# calculator.net
KiCad netlist of a schematic drawn in EAGLE
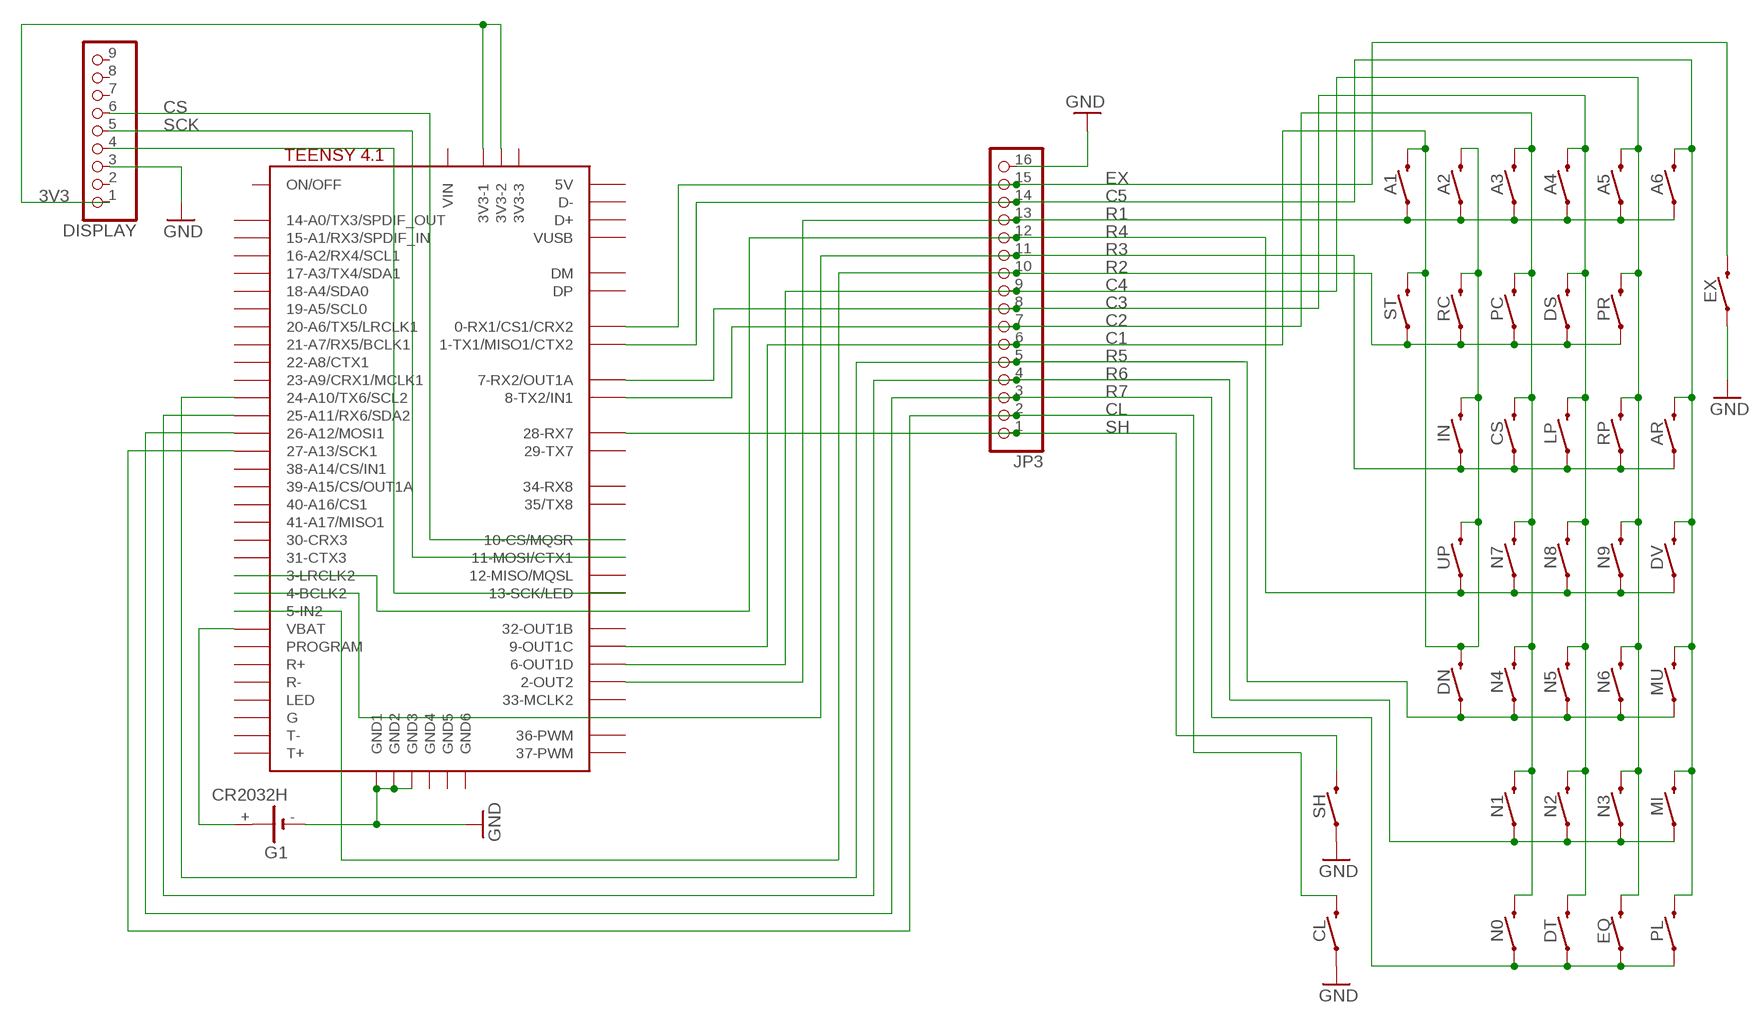
[diagram p0: schematic, sheet 1]

(export (version "E")
  (design (tool "Eeschema 10.0.6"))
  (components
    (comp (ref "A1")
      (value "MOMENTARY-SWITCH-SPST-PTH-6.0MM")
      (footprint "eagle-import:TACTILE_SWITCH_PTH_6.0MM")
      (libsource (lib "eagle-import") (part "MOMENTARY-SWITCH-SPST-PTH-6.0MM"))
    )
    (comp (ref "A2")
      (value "MOMENTARY-SWITCH-SPST-PTH-6.0MM")
      (footprint "eagle-import:TACTILE_SWITCH_PTH_6.0MM")
      (libsource (lib "eagle-import") (part "MOMENTARY-SWITCH-SPST-PTH-6.0MM"))
    )
    (comp (ref "A3")
      (value "MOMENTARY-SWITCH-SPST-PTH-6.0MM")
      (footprint "eagle-import:TACTILE_SWITCH_PTH_6.0MM")
      (libsource (lib "eagle-import") (part "MOMENTARY-SWITCH-SPST-PTH-6.0MM"))
    )
    (comp (ref "A4")
      (value "MOMENTARY-SWITCH-SPST-PTH-6.0MM")
      (footprint "eagle-import:TACTILE_SWITCH_PTH_6.0MM")
      (libsource (lib "eagle-import") (part "MOMENTARY-SWITCH-SPST-PTH-6.0MM"))
    )
    (comp (ref "A5")
      (value "MOMENTARY-SWITCH-SPST-PTH-6.0MM")
      (footprint "eagle-import:TACTILE_SWITCH_PTH_6.0MM")
      (libsource (lib "eagle-import") (part "MOMENTARY-SWITCH-SPST-PTH-6.0MM"))
    )
    (comp (ref "A6")
      (value "MOMENTARY-SWITCH-SPST-PTH-6.0MM")
      (footprint "eagle-import:TACTILE_SWITCH_PTH_6.0MM")
      (libsource (lib "eagle-import") (part "MOMENTARY-SWITCH-SPST-PTH-6.0MM"))
    )
    (comp (ref "AR")
      (value "MOMENTARY-SWITCH-SPST-PTH-6.0MM")
      (footprint "eagle-import:TACTILE_SWITCH_PTH_6.0MM")
      (libsource (lib "eagle-import") (part "MOMENTARY-SWITCH-SPST-PTH-6.0MM"))
    )
    (comp (ref "CL")
      (value "MOMENTARY-SWITCH-SPST-PTH-6.0MM")
      (footprint "eagle-import:TACTILE_SWITCH_PTH_6.0MM")
      (libsource (lib "eagle-import") (part "MOMENTARY-SWITCH-SPST-PTH-6.0MM"))
    )
    (comp (ref "CS")
      (value "MOMENTARY-SWITCH-SPST-PTH-6.0MM")
      (footprint "eagle-import:TACTILE_SWITCH_PTH_6.0MM")
      (libsource (lib "eagle-import") (part "MOMENTARY-SWITCH-SPST-PTH-6.0MM"))
    )
    (comp (ref "DISPLAY")
      (value "PINHD-1X9")
      (footprint "eagle-import:1X09-BIG")
      (libsource (lib "eagle-import") (part "PINHD-1X9"))
    )
    (comp (ref "DN")
      (value "MOMENTARY-SWITCH-SPST-PTH-6.0MM")
      (footprint "eagle-import:TACTILE_SWITCH_PTH_6.0MM")
      (libsource (lib "eagle-import") (part "MOMENTARY-SWITCH-SPST-PTH-6.0MM"))
    )
    (comp (ref "DS")
      (value "MOMENTARY-SWITCH-SPST-PTH-6.0MM")
      (footprint "eagle-import:TACTILE_SWITCH_PTH_6.0MM")
      (libsource (lib "eagle-import") (part "MOMENTARY-SWITCH-SPST-PTH-6.0MM"))
    )
    (comp (ref "DT")
      (value "MOMENTARY-SWITCH-SPST-PTH-6.0MM")
      (footprint "eagle-import:TACTILE_SWITCH_PTH_6.0MM")
      (libsource (lib "eagle-import") (part "MOMENTARY-SWITCH-SPST-PTH-6.0MM"))
    )
    (comp (ref "DV")
      (value "MOMENTARY-SWITCH-SPST-PTH-6.0MM")
      (footprint "eagle-import:TACTILE_SWITCH_PTH_6.0MM")
      (libsource (lib "eagle-import") (part "MOMENTARY-SWITCH-SPST-PTH-6.0MM"))
    )
    (comp (ref "EQ")
      (value "MOMENTARY-SWITCH-SPST-PTH-6.0MM")
      (footprint "eagle-import:TACTILE_SWITCH_PTH_6.0MM")
      (libsource (lib "eagle-import") (part "MOMENTARY-SWITCH-SPST-PTH-6.0MM"))
    )
    (comp (ref "EX")
      (value "MOMENTARY-SWITCH-SPST-PTH-6.0MM")
      (footprint "eagle-import:TACTILE_SWITCH_PTH_6.0MM")
      (libsource (lib "eagle-import") (part "MOMENTARY-SWITCH-SPST-PTH-6.0MM"))
    )
    (comp (ref "G1")
      (value "CR2032H")
      (footprint "eagle-import:CR2032H")
      (libsource (lib "eagle-import") (part "CR2032H"))
    )
    (comp (ref "IN")
      (value "MOMENTARY-SWITCH-SPST-PTH-6.0MM")
      (footprint "eagle-import:TACTILE_SWITCH_PTH_6.0MM")
      (libsource (lib "eagle-import") (part "MOMENTARY-SWITCH-SPST-PTH-6.0MM"))
    )
    (comp (ref "JP3")
      (value "PINHD-1X16")
      (footprint "eagle-import:1X16")
      (libsource (lib "eagle-import") (part "PINHD-1X16"))
    )
    (comp (ref "LP")
      (value "MOMENTARY-SWITCH-SPST-PTH-6.0MM")
      (footprint "eagle-import:TACTILE_SWITCH_PTH_6.0MM")
      (libsource (lib "eagle-import") (part "MOMENTARY-SWITCH-SPST-PTH-6.0MM"))
    )
    (comp (ref "MI")
      (value "MOMENTARY-SWITCH-SPST-PTH-6.0MM")
      (footprint "eagle-import:TACTILE_SWITCH_PTH_6.0MM")
      (libsource (lib "eagle-import") (part "MOMENTARY-SWITCH-SPST-PTH-6.0MM"))
    )
    (comp (ref "MU")
      (value "MOMENTARY-SWITCH-SPST-PTH-6.0MM")
      (footprint "eagle-import:TACTILE_SWITCH_PTH_6.0MM")
      (libsource (lib "eagle-import") (part "MOMENTARY-SWITCH-SPST-PTH-6.0MM"))
    )
    (comp (ref "N0")
      (value "MOMENTARY-SWITCH-SPST-PTH-6.0MM")
      (footprint "eagle-import:TACTILE_SWITCH_PTH_6.0MM")
      (libsource (lib "eagle-import") (part "MOMENTARY-SWITCH-SPST-PTH-6.0MM"))
    )
    (comp (ref "N1")
      (value "MOMENTARY-SWITCH-SPST-PTH-6.0MM")
      (footprint "eagle-import:TACTILE_SWITCH_PTH_6.0MM")
      (libsource (lib "eagle-import") (part "MOMENTARY-SWITCH-SPST-PTH-6.0MM"))
    )
    (comp (ref "N2")
      (value "MOMENTARY-SWITCH-SPST-PTH-6.0MM")
      (footprint "eagle-import:TACTILE_SWITCH_PTH_6.0MM")
      (libsource (lib "eagle-import") (part "MOMENTARY-SWITCH-SPST-PTH-6.0MM"))
    )
    (comp (ref "N3")
      (value "MOMENTARY-SWITCH-SPST-PTH-6.0MM")
      (footprint "eagle-import:TACTILE_SWITCH_PTH_6.0MM")
      (libsource (lib "eagle-import") (part "MOMENTARY-SWITCH-SPST-PTH-6.0MM"))
    )
    (comp (ref "N4")
      (value "MOMENTARY-SWITCH-SPST-PTH-6.0MM")
      (footprint "eagle-import:TACTILE_SWITCH_PTH_6.0MM")
      (libsource (lib "eagle-import") (part "MOMENTARY-SWITCH-SPST-PTH-6.0MM"))
    )
    (comp (ref "N5")
      (value "MOMENTARY-SWITCH-SPST-PTH-6.0MM")
      (footprint "eagle-import:TACTILE_SWITCH_PTH_6.0MM")
      (libsource (lib "eagle-import") (part "MOMENTARY-SWITCH-SPST-PTH-6.0MM"))
    )
    (comp (ref "N6")
      (value "MOMENTARY-SWITCH-SPST-PTH-6.0MM")
      (footprint "eagle-import:TACTILE_SWITCH_PTH_6.0MM")
      (libsource (lib "eagle-import") (part "MOMENTARY-SWITCH-SPST-PTH-6.0MM"))
    )
    (comp (ref "N7")
      (value "MOMENTARY-SWITCH-SPST-PTH-6.0MM")
      (footprint "eagle-import:TACTILE_SWITCH_PTH_6.0MM")
      (libsource (lib "eagle-import") (part "MOMENTARY-SWITCH-SPST-PTH-6.0MM"))
    )
    (comp (ref "N8")
      (value "MOMENTARY-SWITCH-SPST-PTH-6.0MM")
      (footprint "eagle-import:TACTILE_SWITCH_PTH_6.0MM")
      (libsource (lib "eagle-import") (part "MOMENTARY-SWITCH-SPST-PTH-6.0MM"))
    )
    (comp (ref "N9")
      (value "MOMENTARY-SWITCH-SPST-PTH-6.0MM")
      (footprint "eagle-import:TACTILE_SWITCH_PTH_6.0MM")
      (libsource (lib "eagle-import") (part "MOMENTARY-SWITCH-SPST-PTH-6.0MM"))
    )
    (comp (ref "PC")
      (value "MOMENTARY-SWITCH-SPST-PTH-6.0MM")
      (footprint "eagle-import:TACTILE_SWITCH_PTH_6.0MM")
      (libsource (lib "eagle-import") (part "MOMENTARY-SWITCH-SPST-PTH-6.0MM"))
    )
    (comp (ref "PL")
      (value "MOMENTARY-SWITCH-SPST-PTH-6.0MM")
      (footprint "eagle-import:TACTILE_SWITCH_PTH_6.0MM")
      (libsource (lib "eagle-import") (part "MOMENTARY-SWITCH-SPST-PTH-6.0MM"))
    )
    (comp (ref "PR")
      (value "MOMENTARY-SWITCH-SPST-PTH-6.0MM")
      (footprint "eagle-import:TACTILE_SWITCH_PTH_6.0MM")
      (libsource (lib "eagle-import") (part "MOMENTARY-SWITCH-SPST-PTH-6.0MM"))
    )
    (comp (ref "RC")
      (value "MOMENTARY-SWITCH-SPST-PTH-6.0MM")
      (footprint "eagle-import:TACTILE_SWITCH_PTH_6.0MM")
      (libsource (lib "eagle-import") (part "MOMENTARY-SWITCH-SPST-PTH-6.0MM"))
    )
    (comp (ref "RP")
      (value "MOMENTARY-SWITCH-SPST-PTH-6.0MM")
      (footprint "eagle-import:TACTILE_SWITCH_PTH_6.0MM")
      (libsource (lib "eagle-import") (part "MOMENTARY-SWITCH-SPST-PTH-6.0MM"))
    )
    (comp (ref "SH")
      (value "MOMENTARY-SWITCH-SPST-PTH-6.0MM")
      (footprint "eagle-import:TACTILE_SWITCH_PTH_6.0MM")
      (libsource (lib "eagle-import") (part "MOMENTARY-SWITCH-SPST-PTH-6.0MM"))
    )
    (comp (ref "ST")
      (value "MOMENTARY-SWITCH-SPST-PTH-6.0MM")
      (footprint "eagle-import:TACTILE_SWITCH_PTH_6.0MM")
      (libsource (lib "eagle-import") (part "MOMENTARY-SWITCH-SPST-PTH-6.0MM"))
    )
    (comp (ref "U$1")
      (value "TEENSY41")
      (footprint "eagle-import:TEENSY41")
      (libsource (lib "eagle-import") (part "TEENSY41"))
    )
    (comp (ref "UP")
      (value "MOMENTARY-SWITCH-SPST-PTH-6.0MM")
      (footprint "eagle-import:TACTILE_SWITCH_PTH_6.0MM")
      (libsource (lib "eagle-import") (part "MOMENTARY-SWITCH-SPST-PTH-6.0MM"))
    )
  )
  (nets
    (net (code "1") (name "/3V3") (class "Default")
      (node (ref "DISPLAY") (pin "1") (pinfunction "1_1") (pintype "passive"))
      (node (ref "U$1") (pin "3V3-1") (pinfunction "3V3-1_3V3-1") (pintype "bidirectional"))
      (node (ref "U$1") (pin "3V3-2") (pinfunction "3V3-2_3V3-2") (pintype "bidirectional"))
    )
    (net (code "2") (name "/C1") (class "Default")
      (node (ref "A1") (pin "3") (pinfunction "2_3") (pintype "passive"))
      (node (ref "A2") (pin "3") (pinfunction "2_3") (pintype "passive"))
      (node (ref "DN") (pin "3") (pinfunction "2_3") (pintype "passive"))
      (node (ref "IN") (pin "3") (pinfunction "2_3") (pintype "passive"))
      (node (ref "JP3") (pin "6") (pinfunction "6_6") (pintype "passive"))
      (node (ref "RC") (pin "3") (pinfunction "2_3") (pintype "passive"))
      (node (ref "ST") (pin "3") (pinfunction "2_3") (pintype "passive"))
      (node (ref "U$1") (pin "9-OUT1C") (pinfunction "9-OUT1C_9-OUT1C") (pintype "bidirectional"))
      (node (ref "UP") (pin "3") (pinfunction "2_3") (pintype "passive"))
    )
    (net (code "3") (name "/C2") (class "Default")
      (node (ref "A3") (pin "3") (pinfunction "2_3") (pintype "passive"))
      (node (ref "CS") (pin "3") (pinfunction "2_3") (pintype "passive"))
      (node (ref "JP3") (pin "7") (pinfunction "7_7") (pintype "passive"))
      (node (ref "N0") (pin "3") (pinfunction "2_3") (pintype "passive"))
      (node (ref "N1") (pin "3") (pinfunction "2_3") (pintype "passive"))
      (node (ref "N4") (pin "3") (pinfunction "2_3") (pintype "passive"))
      (node (ref "N7") (pin "3") (pinfunction "2_3") (pintype "passive"))
      (node (ref "PC") (pin "3") (pinfunction "2_3") (pintype "passive"))
      (node (ref "U$1") (pin "8-TX2/IN2") (pinfunction "8-TX2/IN1_8-TX2/IN2") (pintype "bidirectional"))
    )
    (net (code "4") (name "/C3") (class "Default")
      (node (ref "A4") (pin "3") (pinfunction "2_3") (pintype "passive"))
      (node (ref "DS") (pin "3") (pinfunction "2_3") (pintype "passive"))
      (node (ref "DT") (pin "3") (pinfunction "2_3") (pintype "passive"))
      (node (ref "JP3") (pin "8") (pinfunction "8_8") (pintype "passive"))
      (node (ref "LP") (pin "3") (pinfunction "2_3") (pintype "passive"))
      (node (ref "N2") (pin "3") (pinfunction "2_3") (pintype "passive"))
      (node (ref "N5") (pin "3") (pinfunction "2_3") (pintype "passive"))
      (node (ref "N8") (pin "3") (pinfunction "2_3") (pintype "passive"))
      (node (ref "U$1") (pin "7-RX2/OUT1A") (pinfunction "7-RX2/OUT1A_7-RX2/OUT1A") (pintype "bidirectional"))
    )
    (net (code "5") (name "/C4") (class "Default")
      (node (ref "A5") (pin "3") (pinfunction "2_3") (pintype "passive"))
      (node (ref "EQ") (pin "3") (pinfunction "2_3") (pintype "passive"))
      (node (ref "JP3") (pin "9") (pinfunction "9_9") (pintype "passive"))
      (node (ref "N3") (pin "3") (pinfunction "2_3") (pintype "passive"))
      (node (ref "N6") (pin "3") (pinfunction "2_3") (pintype "passive"))
      (node (ref "N9") (pin "3") (pinfunction "2_3") (pintype "passive"))
      (node (ref "PR") (pin "3") (pinfunction "2_3") (pintype "passive"))
      (node (ref "RP") (pin "3") (pinfunction "2_3") (pintype "passive"))
      (node (ref "U$1") (pin "6-OUT1D") (pinfunction "6-OUT1D_6-OUT1D") (pintype "bidirectional"))
    )
    (net (code "6") (name "/C5") (class "Default")
      (node (ref "A6") (pin "3") (pinfunction "2_3") (pintype "passive"))
      (node (ref "AR") (pin "3") (pinfunction "2_3") (pintype "passive"))
      (node (ref "DV") (pin "3") (pinfunction "2_3") (pintype "passive"))
      (node (ref "JP3") (pin "14") (pinfunction "14_14") (pintype "passive"))
      (node (ref "MI") (pin "3") (pinfunction "2_3") (pintype "passive"))
      (node (ref "MU") (pin "3") (pinfunction "2_3") (pintype "passive"))
      (node (ref "PL") (pin "3") (pinfunction "2_3") (pintype "passive"))
      (node (ref "U$1") (pin "1-TX1/MISO1/CTX2") (pinfunction "1-TX1/MISO1/CTX2_1-TX1/MISO1/CTX2") (pintype "bidirectional"))
    )
    (net (code "7") (name "/CL") (class "Default")
      (node (ref "CL") (pin "3") (pinfunction "2_3") (pintype "passive"))
      (node (ref "JP3") (pin "2") (pinfunction "2_2") (pintype "passive"))
      (node (ref "U$1") (pin "27-A13/SCK1") (pinfunction "27-A13/SCK1_27-A13/SCK1") (pintype "bidirectional"))
    )
    (net (code "8") (name "/CS") (class "Default")
      (node (ref "DISPLAY") (pin "6") (pinfunction "6_6") (pintype "passive"))
      (node (ref "U$1") (pin "10-CS\\MQSR") (pinfunction "10-CS/MQSR_10-CS\\MQSR") (pintype "bidirectional"))
    )
    (net (code "9") (name "/EX") (class "Default")
      (node (ref "EX") (pin "3") (pinfunction "2_3") (pintype "passive"))
      (node (ref "JP3") (pin "15") (pinfunction "15_15") (pintype "passive"))
      (node (ref "U$1") (pin "0-RX1/CS1/CRX2") (pinfunction "0-RX1/CS1/CRX2_0-RX1/CS1/CRX2") (pintype "bidirectional"))
    )
    (net (code "10") (name "/R1") (class "Default")
      (node (ref "A1") (pin "1") (pinfunction "1_1") (pintype "passive"))
      (node (ref "A2") (pin "1") (pinfunction "1_1") (pintype "passive"))
      (node (ref "A3") (pin "1") (pinfunction "1_1") (pintype "passive"))
      (node (ref "A4") (pin "1") (pinfunction "1_1") (pintype "passive"))
      (node (ref "A5") (pin "1") (pinfunction "1_1") (pintype "passive"))
      (node (ref "A6") (pin "1") (pinfunction "1_1") (pintype "passive"))
      (node (ref "JP3") (pin "13") (pinfunction "13_13") (pintype "passive"))
      (node (ref "U$1") (pin "2-OUT2") (pinfunction "2-OUT2_2-OUT2") (pintype "bidirectional"))
    )
    (net (code "11") (name "/R2") (class "Default")
      (node (ref "DS") (pin "1") (pinfunction "1_1") (pintype "passive"))
      (node (ref "JP3") (pin "10") (pinfunction "10_10") (pintype "passive"))
      (node (ref "PC") (pin "1") (pinfunction "1_1") (pintype "passive"))
      (node (ref "PR") (pin "1") (pinfunction "1_1") (pintype "passive"))
      (node (ref "RC") (pin "1") (pinfunction "1_1") (pintype "passive"))
      (node (ref "ST") (pin "1") (pinfunction "1_1") (pintype "passive"))
      (node (ref "U$1") (pin "5-IN2") (pinfunction "5-IN2_5-IN2") (pintype "bidirectional"))
    )
    (net (code "12") (name "/R3") (class "Default")
      (node (ref "AR") (pin "1") (pinfunction "1_1") (pintype "passive"))
      (node (ref "CS") (pin "1") (pinfunction "1_1") (pintype "passive"))
      (node (ref "IN") (pin "1") (pinfunction "1_1") (pintype "passive"))
      (node (ref "JP3") (pin "11") (pinfunction "11_11") (pintype "passive"))
      (node (ref "LP") (pin "1") (pinfunction "1_1") (pintype "passive"))
      (node (ref "RP") (pin "1") (pinfunction "1_1") (pintype "passive"))
      (node (ref "U$1") (pin "4-BCLK2") (pinfunction "4-BCLK2_4-BCLK2") (pintype "bidirectional"))
    )
    (net (code "13") (name "/R4") (class "Default")
      (node (ref "DV") (pin "1") (pinfunction "1_1") (pintype "passive"))
      (node (ref "JP3") (pin "12") (pinfunction "12_12") (pintype "passive"))
      (node (ref "N7") (pin "1") (pinfunction "1_1") (pintype "passive"))
      (node (ref "N8") (pin "1") (pinfunction "1_1") (pintype "passive"))
      (node (ref "N9") (pin "1") (pinfunction "1_1") (pintype "passive"))
      (node (ref "U$1") (pin "3-LRCLK2") (pinfunction "3-LRCLK2_3-LRCLK2") (pintype "bidirectional"))
      (node (ref "UP") (pin "1") (pinfunction "1_1") (pintype "passive"))
    )
    (net (code "14") (name "/R5") (class "Default")
      (node (ref "DN") (pin "1") (pinfunction "1_1") (pintype "passive"))
      (node (ref "JP3") (pin "5") (pinfunction "5_5") (pintype "passive"))
      (node (ref "MU") (pin "1") (pinfunction "1_1") (pintype "passive"))
      (node (ref "N4") (pin "1") (pinfunction "1_1") (pintype "passive"))
      (node (ref "N5") (pin "1") (pinfunction "1_1") (pintype "passive"))
      (node (ref "N6") (pin "1") (pinfunction "1_1") (pintype "passive"))
      (node (ref "U$1") (pin "24-A10/TX6/SCL2") (pinfunction "24-A10/TX6/SCL2_24-A10/TX6/SCL2") (pintype "bidirectional"))
    )
    (net (code "15") (name "/R6") (class "Default")
      (node (ref "JP3") (pin "4") (pinfunction "4_4") (pintype "passive"))
      (node (ref "MI") (pin "1") (pinfunction "1_1") (pintype "passive"))
      (node (ref "N1") (pin "1") (pinfunction "1_1") (pintype "passive"))
      (node (ref "N2") (pin "1") (pinfunction "1_1") (pintype "passive"))
      (node (ref "N3") (pin "1") (pinfunction "1_1") (pintype "passive"))
      (node (ref "U$1") (pin "25-A11/RX6/SDA2") (pinfunction "25-A11/RX6/SDA2_25-A11/RX6/SDA2") (pintype "bidirectional"))
    )
    (net (code "16") (name "/R7") (class "Default")
      (node (ref "DT") (pin "1") (pinfunction "1_1") (pintype "passive"))
      (node (ref "EQ") (pin "1") (pinfunction "1_1") (pintype "passive"))
      (node (ref "JP3") (pin "3") (pinfunction "3_3") (pintype "passive"))
      (node (ref "N0") (pin "1") (pinfunction "1_1") (pintype "passive"))
      (node (ref "PL") (pin "1") (pinfunction "1_1") (pintype "passive"))
      (node (ref "U$1") (pin "26-A12/MOSI1") (pinfunction "26-A12/MOSI1_26-A12/MOSI1") (pintype "bidirectional"))
    )
    (net (code "17") (name "/SCK") (class "Default")
      (node (ref "DISPLAY") (pin "4") (pinfunction "4_4") (pintype "passive"))
      (node (ref "U$1") (pin "13-SCK/LED") (pinfunction "13-SCK/LED_13-SCK/LED") (pintype "bidirectional"))
    )
    (net (code "18") (name "/SH") (class "Default")
      (node (ref "JP3") (pin "1") (pinfunction "1_1") (pintype "passive"))
      (node (ref "SH") (pin "3") (pinfunction "2_3") (pintype "passive"))
      (node (ref "U$1") (pin "28-RX7") (pinfunction "28-RX7_28-RX7") (pintype "bidirectional"))
    )
    (net (code "19") (name "GND") (class "Default")
      (node (ref "CL") (pin "1") (pinfunction "1_1") (pintype "passive"))
      (node (ref "DISPLAY") (pin "3") (pinfunction "3_3") (pintype "passive"))
      (node (ref "EX") (pin "1") (pinfunction "1_1") (pintype "passive"))
      (node (ref "G1") (pin "-") (pinfunction "-_-") (pintype "passive"))
      (node (ref "JP3") (pin "16") (pinfunction "16_16") (pintype "passive"))
      (node (ref "SH") (pin "1") (pinfunction "1_1") (pintype "passive"))
      (node (ref "U$1") (pin "GND1") (pinfunction "GND1_GND1") (pintype "bidirectional"))
      (node (ref "U$1") (pin "GND2") (pinfunction "GND2_GND2") (pintype "bidirectional"))
      (node (ref "U$1") (pin "GND3") (pinfunction "GND3_GND3") (pintype "bidirectional"))
    )
    (net (code "20") (name "Net-(DISPLAY-Pad5)") (class "Default")
      (node (ref "DISPLAY") (pin "5") (pinfunction "5_5") (pintype "passive"))
      (node (ref "U$1") (pin "11-MOSI/CTX1") (pinfunction "11-MOSI/CTX1_11-MOSI/CTX1") (pintype "bidirectional"))
    )
    (net (code "21") (name "Net-(G1-Pad+)") (class "Default")
      (node (ref "G1") (pin "+") (pinfunction "+_+") (pintype "passive"))
      (node (ref "U$1") (pin "VBAT") (pinfunction "VBAT_VBAT") (pintype "bidirectional"))
    )
    (net (code "22") (name "unconnected-(DISPLAY-Pad2)") (class "Default")
      (node (ref "DISPLAY") (pin "2") (pinfunction "2_2") (pintype "passive"))
    )
    (net (code "23") (name "unconnected-(DISPLAY-Pad7)") (class "Default")
      (node (ref "DISPLAY") (pin "7") (pinfunction "7_7") (pintype "passive"))
    )
    (net (code "24") (name "unconnected-(DISPLAY-Pad8)") (class "Default")
      (node (ref "DISPLAY") (pin "8") (pinfunction "8_8") (pintype "passive"))
    )
    (net (code "25") (name "unconnected-(DISPLAY-Pad9)") (class "Default")
      (node (ref "DISPLAY") (pin "9") (pinfunction "9_9") (pintype "passive"))
    )
    (net (code "26") (name "unconnected-(G1-+-Pad+@1)") (class "Default")
      (node (ref "G1") (pin "+@1") (pinfunction "+_+@1") (pintype "passive"))
    )
    (net (code "27") (name "unconnected-(U$1-5V-Pad+5V)") (class "Default")
      (node (ref "U$1") (pin "+5V") (pinfunction "5V_+5V") (pintype "bidirectional"))
    )
    (net (code "28") (name "unconnected-(U$1-35{slash}TX8-Pad35-TX8)") (class "Default")
      (node (ref "U$1") (pin "35-TX8") (pinfunction "35/TX8_35-TX8") (pintype "bidirectional"))
    )
    (net (code "29") (name "unconnected-(U$1-Pad3V3-3)") (class "Default")
      (node (ref "U$1") (pin "3V3-3") (pinfunction "3V3-3_3V3-3") (pintype "bidirectional"))
    )
    (net (code "30") (name "unconnected-(U$1-Pad12-MISO{slash}MQSL)") (class "Default")
      (node (ref "U$1") (pin "12-MISO/MQSL") (pinfunction "12-MISO/MQSL_12-MISO/MQSL") (pintype "bidirectional"))
    )
    (net (code "31") (name "unconnected-(U$1-Pad14-A0{slash}TX3{slash}SPDIF_OUT)") (class "Default")
      (node (ref "U$1") (pin "14-A0/TX3/SPDIF_OUT") (pinfunction "14-A0/TX3/SPDIF_OUT_14-A0/TX3/SPDIF_OUT") (pintype "bidirectional"))
    )
    (net (code "32") (name "unconnected-(U$1-Pad15-A1{slash}RX3{slash}SPDIF_IN)") (class "Default")
      (node (ref "U$1") (pin "15-A1/RX3/SPDIF_IN") (pinfunction "15-A1/RX3/SPDIF_IN_15-A1/RX3/SPDIF_IN") (pintype "bidirectional"))
    )
    (net (code "33") (name "unconnected-(U$1-Pad16-A2{slash}RX4{slash}SCL1)") (class "Default")
      (node (ref "U$1") (pin "16-A2/RX4/SCL1") (pinfunction "16-A2/RX4/SCL1_16-A2/RX4/SCL1") (pintype "bidirectional"))
    )
    (net (code "34") (name "unconnected-(U$1-Pad17-A3{slash}TX4{slash}SDA1)") (class "Default")
      (node (ref "U$1") (pin "17-A3/TX4/SDA1") (pinfunction "17-A3/TX4/SDA1_17-A3/TX4/SDA1") (pintype "bidirectional"))
    )
    (net (code "35") (name "unconnected-(U$1-Pad18-A4{slash}SDA0)") (class "Default")
      (node (ref "U$1") (pin "18-A4/SDA0") (pinfunction "18-A4/SDA0_18-A4/SDA0") (pintype "bidirectional"))
    )
    (net (code "36") (name "unconnected-(U$1-Pad19-A5{slash}SCL0)") (class "Default")
      (node (ref "U$1") (pin "19-A5/SCL0") (pinfunction "19-A5/SCL0_19-A5/SCL0") (pintype "bidirectional"))
    )
    (net (code "37") (name "unconnected-(U$1-Pad20-A6{slash}TX5{slash}LRCLK1)") (class "Default")
      (node (ref "U$1") (pin "20-A6/TX5/LRCLK1") (pinfunction "20-A6/TX5/LRCLK1_20-A6/TX5/LRCLK1") (pintype "bidirectional"))
    )
    (net (code "38") (name "unconnected-(U$1-Pad21-A7{slash}RX5{slash}BCLK1)") (class "Default")
      (node (ref "U$1") (pin "21-A7/RX5/BCLK1") (pinfunction "21-A7/RX5/BCLK1_21-A7/RX5/BCLK1") (pintype "bidirectional"))
    )
    (net (code "39") (name "unconnected-(U$1-Pad22-A8{slash}CTX1)") (class "Default")
      (node (ref "U$1") (pin "22-A8/CTX1") (pinfunction "22-A8/CTX1_22-A8/CTX1") (pintype "bidirectional"))
    )
    (net (code "40") (name "unconnected-(U$1-Pad23-A9{slash}CRX1{slash}MCLK1)") (class "Default")
      (node (ref "U$1") (pin "23-A9/CRX1/MCLK1") (pinfunction "23-A9/CRX1/MCLK1_23-A9/CRX1/MCLK1") (pintype "bidirectional"))
    )
    (net (code "41") (name "unconnected-(U$1-Pad29-TX7)") (class "Default")
      (node (ref "U$1") (pin "29-TX7") (pinfunction "29-TX7_29-TX7") (pintype "bidirectional"))
    )
    (net (code "42") (name "unconnected-(U$1-Pad30-CRX3)") (class "Default")
      (node (ref "U$1") (pin "30-CRX3") (pinfunction "30-CRX3_30-CRX3") (pintype "bidirectional"))
    )
    (net (code "43") (name "unconnected-(U$1-Pad31-CTX3)") (class "Default")
      (node (ref "U$1") (pin "31-CTX3") (pinfunction "31-CTX3_31-CTX3") (pintype "bidirectional"))
    )
    (net (code "44") (name "unconnected-(U$1-Pad32-OUT1B)") (class "Default")
      (node (ref "U$1") (pin "32-OUT1B") (pinfunction "32-OUT1B_32-OUT1B") (pintype "bidirectional"))
    )
    (net (code "45") (name "unconnected-(U$1-Pad33-MCLK2)") (class "Default")
      (node (ref "U$1") (pin "33-MCLK2") (pinfunction "33-MCLK2_33-MCLK2") (pintype "bidirectional"))
    )
    (net (code "46") (name "unconnected-(U$1-Pad34-RX8)") (class "Default")
      (node (ref "U$1") (pin "34-RX8") (pinfunction "34-RX8_34-RX8") (pintype "bidirectional"))
    )
    (net (code "47") (name "unconnected-(U$1-Pad36-PWM)") (class "Default")
      (node (ref "U$1") (pin "36-PWM") (pinfunction "36-PWM_36-PWM") (pintype "bidirectional"))
    )
    (net (code "48") (name "unconnected-(U$1-Pad37-PWM)") (class "Default")
      (node (ref "U$1") (pin "37-PWM") (pinfunction "37-PWM_37-PWM") (pintype "bidirectional"))
    )
    (net (code "49") (name "unconnected-(U$1-Pad38-A14{slash}CS{slash}IN1)") (class "Default")
      (node (ref "U$1") (pin "38-A14/CS/IN1") (pinfunction "38-A14/CS/IN1_38-A14/CS/IN1") (pintype "bidirectional"))
    )
    (net (code "50") (name "unconnected-(U$1-Pad39-A15{slash}CS{slash}OUT1A)") (class "Default")
      (node (ref "U$1") (pin "39-A15/CS/OUT1A") (pinfunction "39-A15/CS/OUT1A_39-A15/CS/OUT1A") (pintype "bidirectional"))
    )
    (net (code "51") (name "unconnected-(U$1-Pad40-A16{slash}CS1)") (class "Default")
      (node (ref "U$1") (pin "40-A16/CS1") (pinfunction "40-A16/CS1_40-A16/CS1") (pintype "bidirectional"))
    )
    (net (code "52") (name "unconnected-(U$1-Pad41-A17{slash}MISO1)") (class "Default")
      (node (ref "U$1") (pin "41-A17/MISO1") (pinfunction "41-A17/MISO1_41-A17/MISO1") (pintype "bidirectional"))
    )
    (net (code "53") (name "unconnected-(U$1-PadD+)") (class "Default")
      (node (ref "U$1") (pin "D+") (pinfunction "D+_D+") (pintype "bidirectional"))
    )
    (net (code "54") (name "unconnected-(U$1-PadD-)") (class "Default")
      (node (ref "U$1") (pin "D-") (pinfunction "D-_D-") (pintype "bidirectional"))
    )
    (net (code "55") (name "unconnected-(U$1-PadDM)") (class "Default")
      (node (ref "U$1") (pin "DM") (pinfunction "DM_DM") (pintype "bidirectional"))
    )
    (net (code "56") (name "unconnected-(U$1-PadDP)") (class "Default")
      (node (ref "U$1") (pin "DP") (pinfunction "DP_DP") (pintype "bidirectional"))
    )
    (net (code "57") (name "unconnected-(U$1-PadG)") (class "Default")
      (node (ref "U$1") (pin "G") (pinfunction "G_G") (pintype "bidirectional"))
    )
    (net (code "58") (name "unconnected-(U$1-PadGND4)") (class "Default")
      (node (ref "U$1") (pin "GND4") (pinfunction "GND4_GND4") (pintype "bidirectional"))
    )
    (net (code "59") (name "unconnected-(U$1-PadGND5)") (class "Default")
      (node (ref "U$1") (pin "GND5") (pinfunction "GND5_GND5") (pintype "bidirectional"))
    )
    (net (code "60") (name "unconnected-(U$1-PadGND6)") (class "Default")
      (node (ref "U$1") (pin "GND6") (pinfunction "GND6_GND6") (pintype "bidirectional"))
    )
    (net (code "61") (name "unconnected-(U$1-PadLED)") (class "Default")
      (node (ref "U$1") (pin "LED") (pinfunction "LED_LED") (pintype "bidirectional"))
    )
    (net (code "62") (name "unconnected-(U$1-PadON{slash}OFF)") (class "Default")
      (node (ref "U$1") (pin "ON/OFF") (pinfunction "ON/OFF_ON/OFF") (pintype "bidirectional"))
    )
    (net (code "63") (name "unconnected-(U$1-PadPROGRAM)") (class "Default")
      (node (ref "U$1") (pin "PROGRAM") (pinfunction "PROGRAM_PROGRAM") (pintype "bidirectional"))
    )
    (net (code "64") (name "unconnected-(U$1-PadR+)") (class "Default")
      (node (ref "U$1") (pin "R+") (pinfunction "R+_R+") (pintype "bidirectional"))
    )
    (net (code "65") (name "unconnected-(U$1-PadR-)") (class "Default")
      (node (ref "U$1") (pin "R-") (pinfunction "R-_R-") (pintype "bidirectional"))
    )
    (net (code "66") (name "unconnected-(U$1-PadT+)") (class "Default")
      (node (ref "U$1") (pin "T+") (pinfunction "T+_T+") (pintype "bidirectional"))
    )
    (net (code "67") (name "unconnected-(U$1-PadT-)") (class "Default")
      (node (ref "U$1") (pin "T-") (pinfunction "T-_T-") (pintype "bidirectional"))
    )
    (net (code "68") (name "unconnected-(U$1-PadVIN)") (class "Default")
      (node (ref "U$1") (pin "VIN") (pinfunction "VIN_VIN") (pintype "bidirectional"))
    )
    (net (code "69") (name "unconnected-(U$1-PadVUSB)") (class "Default")
      (node (ref "U$1") (pin "VUSB") (pinfunction "VUSB_VUSB") (pintype "bidirectional"))
    )
  )
)
